# lp_dht11.net
KiCad netlist of a schematic drawn in EAGLE
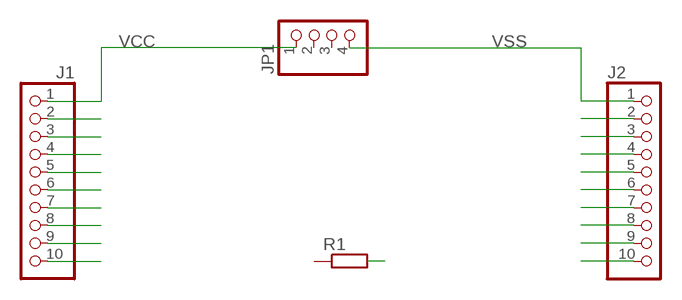
[diagram p0: schematic, sheet 1]

(export (version "E")
  (design (tool "Eeschema 10.0.6"))
  (components
    (comp (ref "J1")
      (value "PH1X10OCT076")
      (footprint "eagle-import:PH1X10OCT76")
      (libsource (lib "eagle-import") (part "PH1X10OCT076"))
    )
    (comp (ref "J2")
      (value "PH1X10OCT076")
      (footprint "eagle-import:PH1X10OCT76")
      (libsource (lib "eagle-import") (part "PH1X10OCT076"))
    )
    (comp (ref "JP1")
      (value "PINHD-1X4")
      (footprint "eagle-import:1X04")
      (libsource (lib "eagle-import") (part "PINHD-1X4"))
    )
    (comp (ref "R1")
      (value "R-EU_0207/10")
      (footprint "eagle-import:0207_10")
      (libsource (lib "eagle-import") (part "R-EU_0207/10"))
    )
  )
  (nets
    (net (code "1") (name "/VCC") (class "Default")
      (node (ref "J1") (pin "1") (pinfunction "1_1") (pintype "passive"))
      (node (ref "JP1") (pin "1") (pinfunction "1_1") (pintype "passive"))
    )
    (net (code "2") (name "/VSS") (class "Default")
      (node (ref "J2") (pin "1") (pinfunction "1_1") (pintype "passive"))
      (node (ref "JP1") (pin "4") (pinfunction "4_4") (pintype "passive"))
    )
    (net (code "3") (name "unconnected-(J1-Pad2)") (class "Default")
      (node (ref "J1") (pin "2") (pinfunction "2_2") (pintype "passive"))
    )
    (net (code "4") (name "unconnected-(J1-Pad3)") (class "Default")
      (node (ref "J1") (pin "3") (pinfunction "3_3") (pintype "passive"))
    )
    (net (code "5") (name "unconnected-(J1-Pad4)") (class "Default")
      (node (ref "J1") (pin "4") (pinfunction "4_4") (pintype "passive"))
    )
    (net (code "6") (name "unconnected-(J1-Pad5)") (class "Default")
      (node (ref "J1") (pin "5") (pinfunction "5_5") (pintype "passive"))
    )
    (net (code "7") (name "unconnected-(J1-Pad6)") (class "Default")
      (node (ref "J1") (pin "6") (pinfunction "6_6") (pintype "passive"))
    )
    (net (code "8") (name "unconnected-(J1-Pad7)") (class "Default")
      (node (ref "J1") (pin "7") (pinfunction "7_7") (pintype "passive"))
    )
    (net (code "9") (name "unconnected-(J1-Pad8)") (class "Default")
      (node (ref "J1") (pin "8") (pinfunction "8_8") (pintype "passive"))
    )
    (net (code "10") (name "unconnected-(J1-Pad9)") (class "Default")
      (node (ref "J1") (pin "9") (pinfunction "9_9") (pintype "passive"))
    )
    (net (code "11") (name "unconnected-(J1-Pad10)") (class "Default")
      (node (ref "J1") (pin "10") (pinfunction "10_10") (pintype "passive"))
    )
    (net (code "12") (name "unconnected-(J2-Pad2)") (class "Default")
      (node (ref "J2") (pin "2") (pinfunction "2_2") (pintype "passive"))
    )
    (net (code "13") (name "unconnected-(J2-Pad3)") (class "Default")
      (node (ref "J2") (pin "3") (pinfunction "3_3") (pintype "passive"))
    )
    (net (code "14") (name "unconnected-(J2-Pad4)") (class "Default")
      (node (ref "J2") (pin "4") (pinfunction "4_4") (pintype "passive"))
    )
    (net (code "15") (name "unconnected-(J2-Pad5)") (class "Default")
      (node (ref "J2") (pin "5") (pinfunction "5_5") (pintype "passive"))
    )
    (net (code "16") (name "unconnected-(J2-Pad6)") (class "Default")
      (node (ref "J2") (pin "6") (pinfunction "6_6") (pintype "passive"))
    )
    (net (code "17") (name "unconnected-(J2-Pad7)") (class "Default")
      (node (ref "J2") (pin "7") (pinfunction "7_7") (pintype "passive"))
    )
    (net (code "18") (name "unconnected-(J2-Pad8)") (class "Default")
      (node (ref "J2") (pin "8") (pinfunction "8_8") (pintype "passive"))
    )
    (net (code "19") (name "unconnected-(J2-Pad9)") (class "Default")
      (node (ref "J2") (pin "9") (pinfunction "9_9") (pintype "passive"))
    )
    (net (code "20") (name "unconnected-(J2-Pad10)") (class "Default")
      (node (ref "J2") (pin "10") (pinfunction "10_10") (pintype "passive"))
    )
    (net (code "21") (name "unconnected-(JP1-Pad2)") (class "Default")
      (node (ref "JP1") (pin "2") (pinfunction "2_2") (pintype "passive"))
    )
    (net (code "22") (name "unconnected-(JP1-Pad3)") (class "Default")
      (node (ref "JP1") (pin "3") (pinfunction "3_3") (pintype "passive"))
    )
    (net (code "23") (name "unconnected-(R1-Pad1)") (class "Default")
      (node (ref "R1") (pin "1") (pinfunction "1_1") (pintype "passive"))
    )
    (net (code "24") (name "unconnected-(R1-Pad2)") (class "Default")
      (node (ref "R1") (pin "2") (pinfunction "2_2") (pintype "passive"))
    )
  )
)
